# ConnectorBoard_r2.net
KiCad netlist of a schematic drawn in Altium Designer
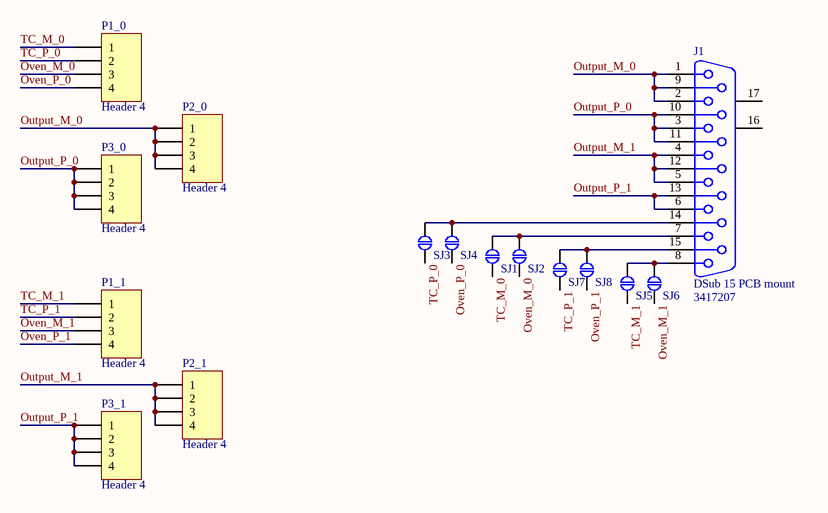
[diagram p0: ConnectorBoard_r2.SchDoc]

(export (version "E")
  (design (tool "Eeschema 10.0.6"))
  (components
    (comp (ref "J1")
      (value "DSub 15 PCB mount")
      (footprint "DSub15-female")
      (fields (field (name "SUPPLIER PART NUMBER 1") "3417207"))
      (libsource (lib "Connectors") (part "DSub 15 PCB mount"))
    )
    (comp (ref "P1_0")
      (value "Header 4")
      (footprint "HDR1X4")
      (description "Header, 4-Pin")
      (fields (field (name "PUBLISHER") "Altium Limited"))
      (libsource (lib "Miscellaneous Connectors") (part "Header 4"))
    )
    (comp (ref "P1_1")
      (value "Header 4")
      (footprint "HDR1X4")
      (description "Header, 4-Pin")
      (fields (field (name "PUBLISHER") "Altium Limited"))
      (libsource (lib "Miscellaneous Connectors") (part "Header 4"))
    )
    (comp (ref "P2_0")
      (value "Header 4")
      (footprint "HDR1X4")
      (description "Header, 4-Pin")
      (fields (field (name "PUBLISHER") "Altium Limited"))
      (libsource (lib "Miscellaneous Connectors") (part "Header 4"))
    )
    (comp (ref "P2_1")
      (value "Header 4")
      (footprint "HDR1X4")
      (description "Header, 4-Pin")
      (fields (field (name "PUBLISHER") "Altium Limited"))
      (libsource (lib "Miscellaneous Connectors") (part "Header 4"))
    )
    (comp (ref "P3_0")
      (value "Header 4")
      (footprint "HDR1X4")
      (description "Header, 4-Pin")
      (fields (field (name "PUBLISHER") "Altium Limited"))
      (libsource (lib "Miscellaneous Connectors") (part "Header 4"))
    )
    (comp (ref "P3_1")
      (value "Header 4")
      (footprint "HDR1X4")
      (description "Header, 4-Pin")
      (fields (field (name "PUBLISHER") "Altium Limited"))
      (libsource (lib "Miscellaneous Connectors") (part "Header 4"))
    )
    (comp (ref "SJ1")
      (value "Solder_jumper")
      (footprint "SOLDER_JUMPER")
      (description "PCB solder jumper")
      (libsource (lib "Misc") (part "Solder_jumper"))
    )
    (comp (ref "SJ2")
      (value "Solder_jumper")
      (footprint "SOLDER_JUMPER")
      (description "PCB solder jumper")
      (libsource (lib "Misc") (part "Solder_jumper"))
    )
    (comp (ref "SJ3")
      (value "Solder_jumper")
      (footprint "SOLDER_JUMPER")
      (description "PCB solder jumper")
      (libsource (lib "Misc") (part "Solder_jumper"))
    )
    (comp (ref "SJ4")
      (value "Solder_jumper")
      (footprint "SOLDER_JUMPER")
      (description "PCB solder jumper")
      (libsource (lib "Misc") (part "Solder_jumper"))
    )
    (comp (ref "SJ5")
      (value "Solder_jumper")
      (footprint "SOLDER_JUMPER")
      (description "PCB solder jumper")
      (libsource (lib "Misc") (part "Solder_jumper"))
    )
    (comp (ref "SJ6")
      (value "Solder_jumper")
      (footprint "SOLDER_JUMPER")
      (description "PCB solder jumper")
      (libsource (lib "Misc") (part "Solder_jumper"))
    )
    (comp (ref "SJ7")
      (value "Solder_jumper")
      (footprint "SOLDER_JUMPER")
      (description "PCB solder jumper")
      (libsource (lib "Misc") (part "Solder_jumper"))
    )
    (comp (ref "SJ8")
      (value "Solder_jumper")
      (footprint "SOLDER_JUMPER")
      (description "PCB solder jumper")
      (libsource (lib "Misc") (part "Solder_jumper"))
    )
  )
  (nets
    (net (code "1") (name "/Output_M_0") (class "Default")
      (node (ref "J1") (pin "1") (pinfunction "1_1") (pintype "passive"))
      (node (ref "J1") (pin "2") (pinfunction "2_2") (pintype "passive"))
      (node (ref "J1") (pin "9") (pinfunction "9_9") (pintype "passive"))
      (node (ref "P2_0") (pin "1") (pinfunction "1_1") (pintype "passive"))
      (node (ref "P2_0") (pin "2") (pinfunction "2_2") (pintype "passive"))
      (node (ref "P2_0") (pin "3") (pinfunction "3_3") (pintype "passive"))
      (node (ref "P2_0") (pin "4") (pinfunction "4_4") (pintype "passive"))
    )
    (net (code "2") (name "/Output_M_1") (class "Default")
      (node (ref "J1") (pin "12") (pinfunction "12_12") (pintype "passive"))
      (node (ref "J1") (pin "4") (pinfunction "4_4") (pintype "passive"))
      (node (ref "J1") (pin "5") (pinfunction "5_5") (pintype "passive"))
      (node (ref "P2_1") (pin "1") (pinfunction "1_1") (pintype "passive"))
      (node (ref "P2_1") (pin "2") (pinfunction "2_2") (pintype "passive"))
      (node (ref "P2_1") (pin "3") (pinfunction "3_3") (pintype "passive"))
      (node (ref "P2_1") (pin "4") (pinfunction "4_4") (pintype "passive"))
    )
    (net (code "3") (name "/Output_P_0") (class "Default")
      (node (ref "J1") (pin "10") (pinfunction "10_10") (pintype "passive"))
      (node (ref "J1") (pin "11") (pinfunction "11_11") (pintype "passive"))
      (node (ref "J1") (pin "3") (pinfunction "3_3") (pintype "passive"))
      (node (ref "P3_0") (pin "1") (pinfunction "1_1") (pintype "passive"))
      (node (ref "P3_0") (pin "2") (pinfunction "2_2") (pintype "passive"))
      (node (ref "P3_0") (pin "3") (pinfunction "3_3") (pintype "passive"))
      (node (ref "P3_0") (pin "4") (pinfunction "4_4") (pintype "passive"))
    )
    (net (code "4") (name "/Output_P_1") (class "Default")
      (node (ref "J1") (pin "13") (pinfunction "13_13") (pintype "passive"))
      (node (ref "J1") (pin "6") (pinfunction "6_6") (pintype "passive"))
      (node (ref "P3_1") (pin "1") (pinfunction "1_1") (pintype "passive"))
      (node (ref "P3_1") (pin "2") (pinfunction "2_2") (pintype "passive"))
      (node (ref "P3_1") (pin "3") (pinfunction "3_3") (pintype "passive"))
      (node (ref "P3_1") (pin "4") (pinfunction "4_4") (pintype "passive"))
    )
    (net (code "5") (name "/Oven_M_0") (class "Default")
      (node (ref "P1_0") (pin "3") (pinfunction "3_3") (pintype "passive"))
      (node (ref "SJ2") (pin "1") (pinfunction "1_1") (pintype "passive"))
    )
    (net (code "6") (name "/Oven_M_1") (class "Default")
      (node (ref "P1_1") (pin "3") (pinfunction "3_3") (pintype "passive"))
      (node (ref "SJ6") (pin "1") (pinfunction "1_1") (pintype "passive"))
    )
    (net (code "7") (name "/Oven_P_0") (class "Default")
      (node (ref "P1_0") (pin "4") (pinfunction "4_4") (pintype "passive"))
      (node (ref "SJ4") (pin "1") (pinfunction "1_1") (pintype "passive"))
    )
    (net (code "8") (name "/Oven_P_1") (class "Default")
      (node (ref "P1_1") (pin "4") (pinfunction "4_4") (pintype "passive"))
      (node (ref "SJ8") (pin "1") (pinfunction "1_1") (pintype "passive"))
    )
    (net (code "9") (name "/TC_M_0") (class "Default")
      (node (ref "P1_0") (pin "1") (pinfunction "1_1") (pintype "passive"))
      (node (ref "SJ1") (pin "1") (pinfunction "1_1") (pintype "passive"))
    )
    (net (code "10") (name "/TC_M_1") (class "Default")
      (node (ref "P1_1") (pin "1") (pinfunction "1_1") (pintype "passive"))
      (node (ref "SJ5") (pin "1") (pinfunction "1_1") (pintype "passive"))
    )
    (net (code "11") (name "/TC_P_0") (class "Default")
      (node (ref "P1_0") (pin "2") (pinfunction "2_2") (pintype "passive"))
      (node (ref "SJ3") (pin "1") (pinfunction "1_1") (pintype "passive"))
    )
    (net (code "12") (name "/TC_P_1") (class "Default")
      (node (ref "P1_1") (pin "2") (pinfunction "2_2") (pintype "passive"))
      (node (ref "SJ7") (pin "1") (pinfunction "1_1") (pintype "passive"))
    )
    (net (code "13") (name "Net-(J1-Pad7)") (class "Default")
      (node (ref "J1") (pin "7") (pinfunction "7_7") (pintype "passive"))
      (node (ref "SJ1") (pin "2") (pinfunction "2_2") (pintype "passive"))
      (node (ref "SJ2") (pin "2") (pinfunction "2_2") (pintype "passive"))
    )
    (net (code "14") (name "Net-(J1-Pad8)") (class "Default")
      (node (ref "J1") (pin "8") (pinfunction "8_8") (pintype "passive"))
      (node (ref "SJ5") (pin "2") (pinfunction "2_2") (pintype "passive"))
      (node (ref "SJ6") (pin "2") (pinfunction "2_2") (pintype "passive"))
    )
    (net (code "15") (name "Net-(J1-Pad14)") (class "Default")
      (node (ref "J1") (pin "14") (pinfunction "14_14") (pintype "passive"))
      (node (ref "SJ3") (pin "2") (pinfunction "2_2") (pintype "passive"))
      (node (ref "SJ4") (pin "2") (pinfunction "2_2") (pintype "passive"))
    )
    (net (code "16") (name "Net-(J1-Pad15)") (class "Default")
      (node (ref "J1") (pin "15") (pinfunction "15_15") (pintype "passive"))
      (node (ref "SJ7") (pin "2") (pinfunction "2_2") (pintype "passive"))
      (node (ref "SJ8") (pin "2") (pinfunction "2_2") (pintype "passive"))
    )
    (net (code "17") (name "unconnected-(J1-MH1-Pad16)") (class "Default")
      (node (ref "J1") (pin "16") (pinfunction "MH1_16") (pintype "passive"))
    )
    (net (code "18") (name "unconnected-(J1-MH2-Pad17)") (class "Default")
      (node (ref "J1") (pin "17") (pinfunction "MH2_17") (pintype "passive"))
    )
  )
)
